# sensor_board_v0_8.net
KiCad netlist of a schematic drawn in EAGLE
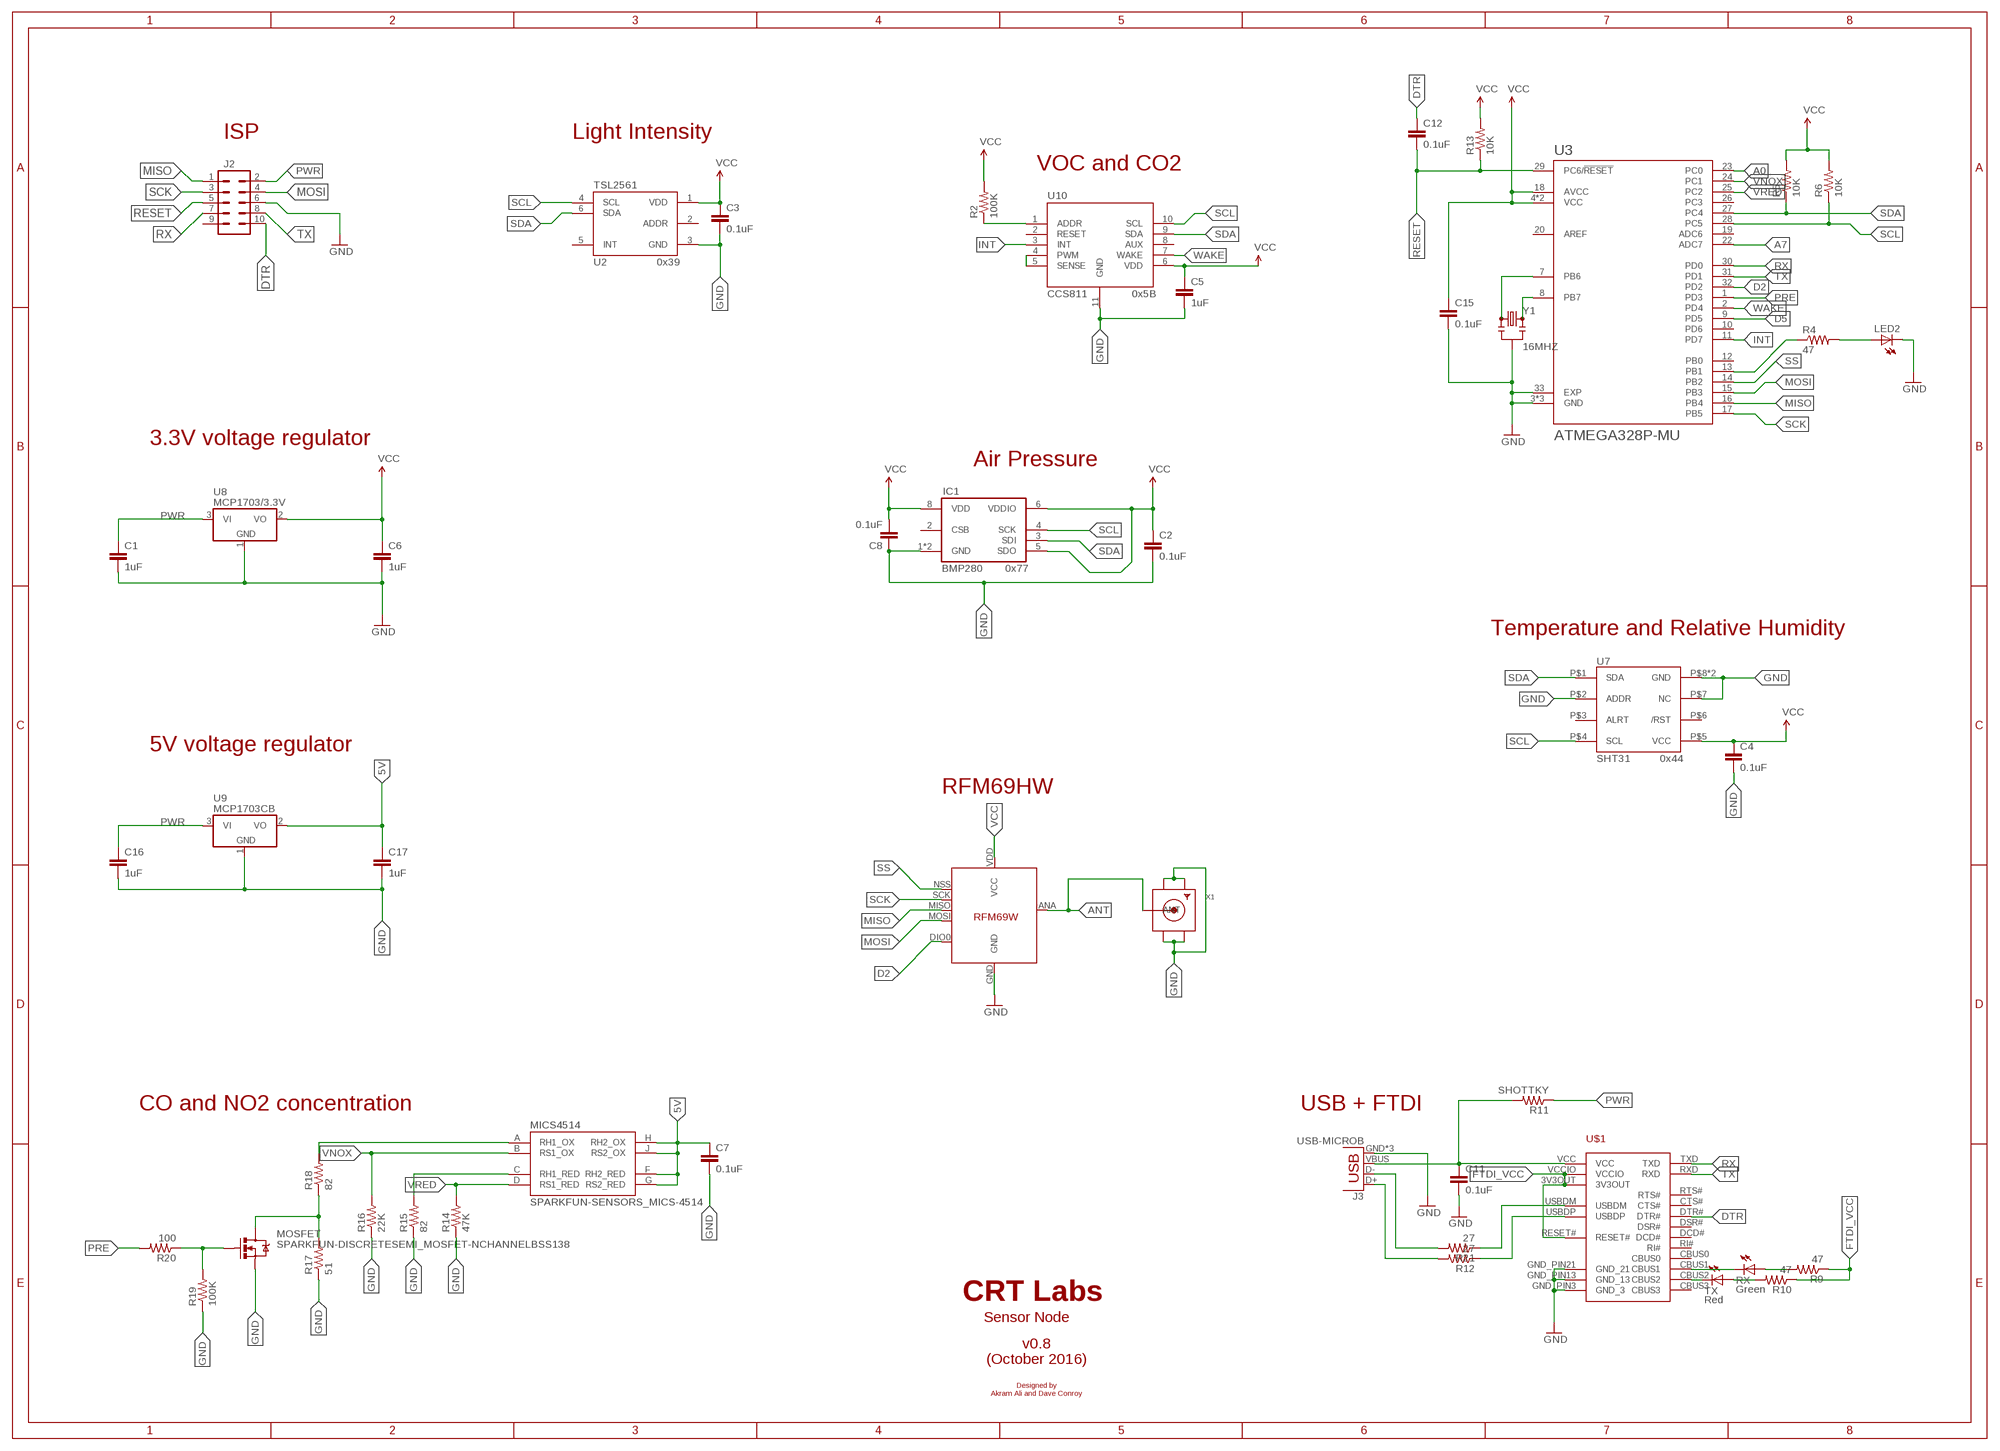
[diagram p0: schematic, sheet 1]

(export (version "E")
  (design (tool "Eeschema 10.0.6"))
  (components
    (comp (ref "C1")
      (value "1uF")
      (footprint "eagle-import:0805")
      (libsource (lib "eagle-import") (part "CAP0805"))
    )
    (comp (ref "C2")
      (value "0.1uF")
      (footprint "eagle-import:0805")
      (libsource (lib "eagle-import") (part "SparkFun-Passives_CAP0805"))
    )
    (comp (ref "C3")
      (value "0.1uF")
      (footprint "eagle-import:0805")
      (libsource (lib "eagle-import") (part "SparkFun-Passives_CAP0805"))
    )
    (comp (ref "C4")
      (value "0.1uF")
      (footprint "eagle-import:0805")
      (libsource (lib "eagle-import") (part "SparkFun-Passives_CAP0805"))
    )
    (comp (ref "C5")
      (value "1uF")
      (footprint "eagle-import:0805")
      (libsource (lib "eagle-import") (part "SparkFun-Passives_CAP0805"))
    )
    (comp (ref "C6")
      (value "1uF")
      (footprint "eagle-import:0805")
      (libsource (lib "eagle-import") (part "CAP0805"))
    )
    (comp (ref "C7")
      (value "0.1uF")
      (footprint "eagle-import:0805")
      (libsource (lib "eagle-import") (part "SparkFun-Passives_CAP0805"))
    )
    (comp (ref "C8")
      (value "0.1uF")
      (footprint "eagle-import:0805")
      (libsource (lib "eagle-import") (part "SparkFun-Passives_CAP0805"))
    )
    (comp (ref "C11")
      (value "0.1uF")
      (footprint "eagle-import:0805")
      (libsource (lib "eagle-import") (part "CAP0805"))
    )
    (comp (ref "C12")
      (value "0.1uF")
      (footprint "eagle-import:0805")
      (libsource (lib "eagle-import") (part "SparkFun-Passives_CAP0805"))
    )
    (comp (ref "C15")
      (value "0.1uF")
      (footprint "eagle-import:0805")
      (libsource (lib "eagle-import") (part "SparkFun-Passives_CAP0805"))
    )
    (comp (ref "C16")
      (value "1uF")
      (footprint "eagle-import:0805")
      (libsource (lib "eagle-import") (part "CAP0805"))
    )
    (comp (ref "C17")
      (value "1uF")
      (footprint "eagle-import:0805")
      (libsource (lib "eagle-import") (part "CAP0805"))
    )
    (comp (ref "IC1")
      (value "BMP280")
      (footprint "eagle-import:BMP280")
      (libsource (lib "eagle-import") (part "BMP280"))
    )
    (comp (ref "J2")
      (value "M05X2PTH")
      (footprint "eagle-import:AVR_ICSP")
      (libsource (lib "eagle-import") (part "M05X2PTH"))
    )
    (comp (ref "J3")
      (value "USB-MICROB")
      (footprint "eagle-import:USB-MICROB")
      (libsource (lib "eagle-import") (part "USB-MICROB"))
    )
    (comp (ref "LED2")
      (value "LEDCHIPLED_0805")
      (footprint "eagle-import:CHIPLED_0805")
      (libsource (lib "eagle-import") (part "LEDCHIPLED_0805"))
    )
    (comp (ref "MICS4514")
      (value "SPARKFUN-SENSORS_MICS-4514")
      (footprint "eagle-import:SPARKFUN-SENSORS_MICS_10-SMD")
      (libsource (lib "eagle-import") (part "SPARKFUN-SENSORS_MICS-4514"))
    )
    (comp (ref "MOSFET")
      (value "SPARKFUN-DISCRETESEMI_MOSFET-NCHANNELBSS138")
      (footprint "eagle-import:SPARKFUN-DISCRETESEMI_SOT23-3")
      (libsource (lib "eagle-import") (part "SPARKFUN-DISCRETESEMI_MOSFET-NCHANNELBSS138"))
    )
    (comp (ref "R2")
      (value "100K")
      (footprint "eagle-import:0805")
      (libsource (lib "eagle-import") (part "RESISTOR0805-RES"))
    )
    (comp (ref "R4")
      (value "47")
      (footprint "eagle-import:0805")
      (libsource (lib "eagle-import") (part "SparkFun-Resistors_RESISTOR0805-RES"))
    )
    (comp (ref "R5")
      (value "10K")
      (footprint "eagle-import:0805")
      (libsource (lib "eagle-import") (part "SparkFun-Resistors_RESISTOR0805-RES"))
    )
    (comp (ref "R6")
      (value "10K")
      (footprint "eagle-import:0805")
      (libsource (lib "eagle-import") (part "SparkFun-Resistors_RESISTOR0805-RES"))
    )
    (comp (ref "R9")
      (value "47")
      (footprint "eagle-import:0805")
      (libsource (lib "eagle-import") (part "RESISTOR0805-RES"))
    )
    (comp (ref "R10")
      (value "47")
      (footprint "eagle-import:0805")
      (libsource (lib "eagle-import") (part "RESISTOR0805-RES"))
    )
    (comp (ref "R11")
      (value "SHOTTKY")
      (footprint "eagle-import:0805")
      (libsource (lib "eagle-import") (part "RESISTOR0805-RES"))
    )
    (comp (ref "R12")
      (value "27")
      (footprint "eagle-import:0805")
      (libsource (lib "eagle-import") (part "RESISTOR0805-RES"))
    )
    (comp (ref "R13")
      (value "10K")
      (footprint "eagle-import:0805")
      (libsource (lib "eagle-import") (part "RESISTOR0805-RES"))
    )
    (comp (ref "R14")
      (value "47K")
      (footprint "eagle-import:0805")
      (libsource (lib "eagle-import") (part "RESISTOR0805-RES"))
    )
    (comp (ref "R15")
      (value "82")
      (footprint "eagle-import:0805")
      (libsource (lib "eagle-import") (part "RESISTOR0805-RES"))
    )
    (comp (ref "R16")
      (value "22K")
      (footprint "eagle-import:0805")
      (libsource (lib "eagle-import") (part "RESISTOR0805-RES"))
    )
    (comp (ref "R17")
      (value "51")
      (footprint "eagle-import:0805")
      (libsource (lib "eagle-import") (part "RESISTOR0805-RES"))
    )
    (comp (ref "R18")
      (value "82")
      (footprint "eagle-import:0805")
      (libsource (lib "eagle-import") (part "RESISTOR0805-RES"))
    )
    (comp (ref "R19")
      (value "100K")
      (footprint "eagle-import:0805")
      (libsource (lib "eagle-import") (part "RESISTOR0805-RES"))
    )
    (comp (ref "R20")
      (value "100")
      (footprint "eagle-import:0805")
      (libsource (lib "eagle-import") (part "RESISTOR0805-RES"))
    )
    (comp (ref "R21")
      (value "27")
      (footprint "eagle-import:0805")
      (libsource (lib "eagle-import") (part "RESISTOR0805-RES"))
    )
    (comp (ref "RX")
      (value "Green")
      (footprint "eagle-import:CHIPLED_0805")
      (libsource (lib "eagle-import") (part "LEDCHIPLED_0805"))
    )
    (comp (ref "TX")
      (value "Red")
      (footprint "eagle-import:CHIPLED_0805")
      (libsource (lib "eagle-import") (part "LEDCHIPLED_0805"))
    )
    (comp (ref "U$1")
      (value "FT231XQ-R")
      (footprint "eagle-import:FTDI_FT231XQ-R_PACKAGE")
      (libsource (lib "eagle-import") (part "FT231XQ-R"))
    )
    (comp (ref "U2")
      (value "TSL2561")
      (footprint "eagle-import:FN-6")
      (fields (field (name "MANF") "AMS-TAOS-USA-Inc.") (field (name "MPN") "TSL2561FN"))
      (libsource (lib "eagle-import") (part "TSL2561FN"))
    )
    (comp (ref "U3")
      (value "ATMEGA328P-MU")
      (footprint "eagle-import:QFN50P500X500X100-33N")
      (fields (field (name "MF") "Atmel"))
      (libsource (lib "eagle-import") (part "ATMEGA328P-MU"))
    )
    (comp (ref "U7")
      (value "SHT31")
      (footprint "eagle-import:SHT3X")
      (fields (field (name "MPN") "SHT31-DIS-B"))
      (libsource (lib "eagle-import") (part "SHT31-DIS"))
    )
    (comp (ref "U8")
      (value "MCP1703/3.3V")
      (footprint "eagle-import:SOT23")
      (fields (field (name "MPN") "MCP1703T-2502E/CB"))
      (libsource (lib "eagle-import") (part "MCP1703CB"))
    )
    (comp (ref "U9")
      (value "MCP1703CB")
      (footprint "eagle-import:SOT23")
      (fields (field (name "MPN") "MCP1703T-2502E/CB"))
      (libsource (lib "eagle-import") (part "MCP1703CB"))
    )
    (comp (ref "U10")
      (value "CCS811")
      (footprint "eagle-import:LGA")
      (libsource (lib "eagle-import") (part "CCS811-I2C"))
    )
    (comp (ref "U11")
      (value "RFM69HW")
      (footprint "eagle-import:LOWPOWERLAB_RFM69W-MINPADS")
      (libsource (lib "eagle-import") (part "LOWPOWERLAB_RFM69"))
    )
    (comp (ref "X1")
      (value "SMACONNECTOR_EDGE")
      (footprint "eagle-import:SMA_EDGELAUNCH")
      (libsource (lib "eagle-import") (part "SMACONNECTOR_EDGE"))
    )
    (comp (ref "Y1")
      (value "16MHZ")
      (footprint "eagle-import:RESONATOR-SMD")
      (libsource (lib "eagle-import") (part "RESONATOR16MHZ"))
    )
  )
  (nets
    (net (code "1") (name "5V") (class "Default")
      (node (ref "C17") (pin "1") (pinfunction "1_1") (pintype "passive"))
      (node (ref "C7") (pin "1") (pinfunction "1_1") (pintype "passive"))
      (node (ref "MICS4514") (pin "F") (pinfunction "RH2_RED_F") (pintype "bidirectional"))
      (node (ref "MICS4514") (pin "G") (pinfunction "RS2_RED_G") (pintype "bidirectional"))
      (node (ref "MICS4514") (pin "H") (pinfunction "RH2_OX_H") (pintype "bidirectional"))
      (node (ref "MICS4514") (pin "J") (pinfunction "RS2_OX_J") (pintype "bidirectional"))
      (node (ref "U9") (pin "2") (pinfunction "VO_2") (pintype "passive"))
    )
    (net (code "2") (name "A0") (class "Default")
      (node (ref "U3") (pin "23") (pinfunction "PC0_23") (pintype "bidirectional"))
    )
    (net (code "3") (name "A7") (class "Default")
      (node (ref "U3") (pin "22") (pinfunction "ADC7_22") (pintype "bidirectional"))
    )
    (net (code "4") (name "ANT") (class "Default")
      (node (ref "U11") (pin "ANA") (pinfunction "ANT_ANA") (pintype "passive"))
      (node (ref "X1") (pin "P") (pinfunction "ANT_P") (pintype "bidirectional"))
    )
    (net (code "5") (name "D2") (class "Default")
      (node (ref "U11") (pin "DIO0") (pinfunction "DIO0_DIO0") (pintype "open_collector"))
      (node (ref "U3") (pin "32") (pinfunction "PD2_32") (pintype "bidirectional"))
    )
    (net (code "6") (name "D5") (class "Default")
      (node (ref "U3") (pin "9") (pinfunction "PD5_9") (pintype "bidirectional"))
    )
    (net (code "7") (name "DTR") (class "Default")
      (node (ref "C12") (pin "1") (pinfunction "1_1") (pintype "passive"))
      (node (ref "J2") (pin "10") (pinfunction "10_10") (pintype "passive"))
      (node (ref "U$1") (pin "DTR#") (pinfunction "DTR#_DTR#") (pintype "bidirectional"))
    )
    (net (code "8") (name "FTDI_VCC") (class "Default")
      (node (ref "R10") (pin "1") (pinfunction "1_1") (pintype "passive"))
      (node (ref "R9") (pin "1") (pinfunction "1_1") (pintype "passive"))
      (node (ref "U$1") (pin "3V3OUT") (pinfunction "3V3OUT_3V3OUT") (pintype "bidirectional"))
      (node (ref "U$1") (pin "RESET#") (pinfunction "RESET#_RESET#") (pintype "bidirectional"))
      (node (ref "U$1") (pin "VCCIO") (pinfunction "VCCIO_VCCIO") (pintype "bidirectional"))
    )
    (net (code "9") (name "GND") (class "Default")
      (node (ref "C1") (pin "2") (pinfunction "2_2") (pintype "passive"))
      (node (ref "C11") (pin "2") (pinfunction "2_2") (pintype "passive"))
      (node (ref "C15") (pin "2") (pinfunction "2_2") (pintype "passive"))
      (node (ref "C16") (pin "2") (pinfunction "2_2") (pintype "passive"))
      (node (ref "C17") (pin "2") (pinfunction "2_2") (pintype "passive"))
      (node (ref "C2") (pin "2") (pinfunction "2_2") (pintype "passive"))
      (node (ref "C3") (pin "2") (pinfunction "2_2") (pintype "passive"))
      (node (ref "C4") (pin "2") (pinfunction "2_2") (pintype "passive"))
      (node (ref "C5") (pin "2") (pinfunction "2_2") (pintype "passive"))
      (node (ref "C6") (pin "2") (pinfunction "2_2") (pintype "passive"))
      (node (ref "C7") (pin "2") (pinfunction "2_2") (pintype "passive"))
      (node (ref "C8") (pin "1") (pinfunction "1_1") (pintype "passive"))
      (node (ref "IC1") (pin "1") (pinfunction "GND_1") (pintype "power_in"))
      (node (ref "IC1") (pin "7") (pinfunction "GND_7") (pintype "power_in"))
      (node (ref "J2") (pin "6") (pinfunction "6_6") (pintype "passive"))
      (node (ref "J3") (pin "GND") (pinfunction "GND_GND") (pintype "bidirectional"))
      (node (ref "J3") (pin "MT1") (pinfunction "GND_MT1") (pintype "bidirectional"))
      (node (ref "J3") (pin "MT2") (pinfunction "GND_MT2") (pintype "bidirectional"))
      (node (ref "LED2") (pin "C") (pinfunction "C_C") (pintype "passive"))
      (node (ref "MOSFET") (pin "2") (pinfunction "S_2") (pintype "passive"))
      (node (ref "R14") (pin "1") (pinfunction "1_1") (pintype "passive"))
      (node (ref "R15") (pin "1") (pinfunction "1_1") (pintype "passive"))
      (node (ref "R16") (pin "1") (pinfunction "1_1") (pintype "passive"))
      (node (ref "R17") (pin "1") (pinfunction "1_1") (pintype "passive"))
      (node (ref "R19") (pin "1") (pinfunction "1_1") (pintype "passive"))
      (node (ref "U$1") (pin "GND_PIN13") (pinfunction "GND_13_GND_PIN13") (pintype "bidirectional"))
      (node (ref "U$1") (pin "GND_PIN21") (pinfunction "GND_21_GND_PIN21") (pintype "bidirectional"))
      (node (ref "U$1") (pin "GND_PIN3") (pinfunction "GND_3_GND_PIN3") (pintype "bidirectional"))
      (node (ref "U10") (pin "11") (pinfunction "GND_11") (pintype "bidirectional"))
      (node (ref "U11") (pin "GND") (pinfunction "GND_GND") (pintype "power_in"))
      (node (ref "U2") (pin "3") (pinfunction "GND_3") (pintype "power_in"))
      (node (ref "U3") (pin "21") (pinfunction "GND_21") (pintype "power_in"))
      (node (ref "U3") (pin "3") (pinfunction "GND_3") (pintype "power_in"))
      (node (ref "U3") (pin "33") (pinfunction "EXP_33") (pintype "power_in"))
      (node (ref "U3") (pin "5") (pinfunction "GND_5") (pintype "power_in"))
      (node (ref "U7") (pin "P$2") (pinfunction "ADDR_P$2") (pintype "bidirectional"))
      (node (ref "U7") (pin "P$7") (pinfunction "NC_P$7") (pintype "bidirectional"))
      (node (ref "U7") (pin "P$8") (pinfunction "GND_P$8") (pintype "bidirectional"))
      (node (ref "U7") (pin "PAD") (pinfunction "GND_PAD") (pintype "bidirectional"))
      (node (ref "U8") (pin "1") (pinfunction "GND_1") (pintype "passive"))
      (node (ref "U9") (pin "1") (pinfunction "GND_1") (pintype "passive"))
      (node (ref "X1") (pin "GND@1") (pinfunction "GND4_GND@1") (pintype "power_in"))
      (node (ref "X1") (pin "GND@2") (pinfunction "GND3_GND@2") (pintype "power_in"))
      (node (ref "X1") (pin "GND@3") (pinfunction "GND2_GND@3") (pintype "power_in"))
      (node (ref "X1") (pin "GND@4") (pinfunction "GND1_GND@4") (pintype "power_in"))
      (node (ref "Y1") (pin "2") (pinfunction "2_2") (pintype "passive"))
    )
    (net (code "10") (name "INT") (class "Default")
      (node (ref "U10") (pin "3") (pinfunction "INT_3") (pintype "bidirectional"))
      (node (ref "U3") (pin "11") (pinfunction "PD7_11") (pintype "bidirectional"))
    )
    (net (code "11") (name "MISO") (class "Default")
      (node (ref "J2") (pin "1") (pinfunction "1_1") (pintype "passive"))
      (node (ref "U11") (pin "MISO") (pinfunction "MISO_MISO") (pintype "input"))
      (node (ref "U3") (pin "16") (pinfunction "PB4_16") (pintype "bidirectional"))
    )
    (net (code "12") (name "MOSI") (class "Default")
      (node (ref "J2") (pin "4") (pinfunction "4_4") (pintype "passive"))
      (node (ref "U11") (pin "MOSI") (pinfunction "MOSI_MOSI") (pintype "output"))
      (node (ref "U3") (pin "15") (pinfunction "PB3_15") (pintype "bidirectional"))
    )
    (net (code "13") (name "Net-(C11-Pad1)") (class "Default")
      (node (ref "C11") (pin "1") (pinfunction "1_1") (pintype "passive"))
      (node (ref "J3") (pin "VBUS") (pinfunction "VBUS_VBUS") (pintype "bidirectional"))
      (node (ref "R11") (pin "2") (pinfunction "2_2") (pintype "passive"))
      (node (ref "U$1") (pin "VCC") (pinfunction "VCC_VCC") (pintype "bidirectional"))
    )
    (net (code "14") (name "Net-(J3-PadD+)") (class "Default")
      (node (ref "J3") (pin "D+") (pinfunction "D+_D+") (pintype "bidirectional"))
      (node (ref "R12") (pin "2") (pinfunction "2_2") (pintype "passive"))
    )
    (net (code "15") (name "Net-(J3-PadD-)") (class "Default")
      (node (ref "J3") (pin "D-") (pinfunction "D-_D-") (pintype "bidirectional"))
      (node (ref "R21") (pin "2") (pinfunction "2_2") (pintype "passive"))
    )
    (net (code "16") (name "Net-(LED2-PadA)") (class "Default")
      (node (ref "LED2") (pin "A") (pinfunction "A_A") (pintype "passive"))
      (node (ref "R4") (pin "2") (pinfunction "2_2") (pintype "passive"))
    )
    (net (code "17") (name "Net-(MICS4514-RH1_OX)") (class "Default")
      (node (ref "MICS4514") (pin "A") (pinfunction "RH1_OX_A") (pintype "bidirectional"))
      (node (ref "R18") (pin "2") (pinfunction "2_2") (pintype "passive"))
    )
    (net (code "18") (name "Net-(MICS4514-RH1_RED)") (class "Default")
      (node (ref "MICS4514") (pin "C") (pinfunction "RH1_RED_C") (pintype "bidirectional"))
      (node (ref "R15") (pin "2") (pinfunction "2_2") (pintype "passive"))
    )
    (net (code "19") (name "Net-(MOSFET-D)") (class "Default")
      (node (ref "MOSFET") (pin "3") (pinfunction "D_3") (pintype "passive"))
      (node (ref "R17") (pin "2") (pinfunction "2_2") (pintype "passive"))
      (node (ref "R18") (pin "1") (pinfunction "1_1") (pintype "passive"))
    )
    (net (code "20") (name "Net-(MOSFET-G)") (class "Default")
      (node (ref "MOSFET") (pin "1") (pinfunction "G_1") (pintype "passive"))
      (node (ref "R19") (pin "2") (pinfunction "2_2") (pintype "passive"))
      (node (ref "R20") (pin "1") (pinfunction "1_1") (pintype "passive"))
    )
    (net (code "21") (name "Net-(R9-Pad2)") (class "Default")
      (node (ref "R9") (pin "2") (pinfunction "2_2") (pintype "passive"))
      (node (ref "RX") (pin "A") (pinfunction "A_A") (pintype "passive"))
    )
    (net (code "22") (name "Net-(R10-Pad2)") (class "Default")
      (node (ref "R10") (pin "2") (pinfunction "2_2") (pintype "passive"))
      (node (ref "TX") (pin "A") (pinfunction "A_A") (pintype "passive"))
    )
    (net (code "23") (name "Net-(R12-Pad1)") (class "Default")
      (node (ref "R12") (pin "1") (pinfunction "1_1") (pintype "passive"))
      (node (ref "U$1") (pin "USBDP") (pinfunction "USBDP_USBDP") (pintype "bidirectional"))
    )
    (net (code "24") (name "Net-(R21-Pad1)") (class "Default")
      (node (ref "R21") (pin "1") (pinfunction "1_1") (pintype "passive"))
      (node (ref "U$1") (pin "USBDM") (pinfunction "USBDM_USBDM") (pintype "bidirectional"))
    )
    (net (code "25") (name "Net-(RX-PadC)") (class "Default")
      (node (ref "RX") (pin "C") (pinfunction "C_C") (pintype "passive"))
      (node (ref "U$1") (pin "CBUS1") (pinfunction "CBUS1_CBUS1") (pintype "bidirectional"))
    )
    (net (code "26") (name "Net-(TX-PadC)") (class "Default")
      (node (ref "TX") (pin "C") (pinfunction "C_C") (pintype "passive"))
      (node (ref "U$1") (pin "CBUS2") (pinfunction "CBUS2_CBUS2") (pintype "bidirectional"))
    )
    (net (code "27") (name "Net-(U3-PB1)") (class "Default")
      (node (ref "R4") (pin "1") (pinfunction "1_1") (pintype "passive"))
      (node (ref "U3") (pin "13") (pinfunction "PB1_13") (pintype "bidirectional"))
    )
    (net (code "28") (name "Net-(U3-PB6)") (class "Default")
      (node (ref "U3") (pin "7") (pinfunction "PB6_7") (pintype "bidirectional"))
      (node (ref "Y1") (pin "1") (pinfunction "1_1") (pintype "passive"))
    )
    (net (code "29") (name "Net-(U3-PB7)") (class "Default")
      (node (ref "U3") (pin "8") (pinfunction "PB7_8") (pintype "bidirectional"))
      (node (ref "Y1") (pin "3") (pinfunction "3_3") (pintype "passive"))
    )
    (net (code "30") (name "Net-(U10-ADDR)") (class "Default")
      (node (ref "R2") (pin "1") (pinfunction "1_1") (pintype "passive"))
      (node (ref "U10") (pin "1") (pinfunction "ADDR_1") (pintype "bidirectional"))
    )
    (net (code "31") (name "Net-(U10-PWM)") (class "Default")
      (node (ref "U10") (pin "4") (pinfunction "PWM_4") (pintype "bidirectional"))
      (node (ref "U10") (pin "5") (pinfunction "SENSE_5") (pintype "bidirectional"))
    )
    (net (code "32") (name "PRE") (class "Default")
      (node (ref "R20") (pin "2") (pinfunction "2_2") (pintype "passive"))
      (node (ref "U3") (pin "1") (pinfunction "PD3_1") (pintype "bidirectional"))
    )
    (net (code "33") (name "PWR") (class "Default")
      (node (ref "C1") (pin "1") (pinfunction "1_1") (pintype "passive"))
      (node (ref "C16") (pin "1") (pinfunction "1_1") (pintype "passive"))
      (node (ref "J2") (pin "2") (pinfunction "2_2") (pintype "passive"))
      (node (ref "R11") (pin "1") (pinfunction "1_1") (pintype "passive"))
      (node (ref "U8") (pin "3") (pinfunction "VI_3") (pintype "input"))
      (node (ref "U9") (pin "3") (pinfunction "VI_3") (pintype "input"))
    )
    (net (code "34") (name "RESET") (class "Default")
      (node (ref "C12") (pin "2") (pinfunction "2_2") (pintype "passive"))
      (node (ref "J2") (pin "5") (pinfunction "5_5") (pintype "passive"))
      (node (ref "R13") (pin "1") (pinfunction "1_1") (pintype "passive"))
      (node (ref "U3") (pin "29") (pinfunction "PC6/~{RESET}_29") (pintype "bidirectional"))
    )
    (net (code "35") (name "RX") (class "Default")
      (node (ref "J2") (pin "7") (pinfunction "7_7") (pintype "passive"))
      (node (ref "U$1") (pin "TXD") (pinfunction "TXD_TXD") (pintype "bidirectional"))
      (node (ref "U3") (pin "30") (pinfunction "PD0_30") (pintype "bidirectional"))
    )
    (net (code "36") (name "SCK") (class "Default")
      (node (ref "J2") (pin "3") (pinfunction "3_3") (pintype "passive"))
      (node (ref "U11") (pin "SCK") (pinfunction "SCK_SCK") (pintype "input"))
      (node (ref "U3") (pin "17") (pinfunction "PB5_17") (pintype "bidirectional"))
    )
    (net (code "37") (name "SCL") (class "Default")
      (node (ref "IC1") (pin "4") (pinfunction "SCK_4") (pintype "bidirectional"))
      (node (ref "R6") (pin "1") (pinfunction "1_1") (pintype "passive"))
      (node (ref "U10") (pin "10") (pinfunction "SCL_10") (pintype "bidirectional"))
      (node (ref "U2") (pin "4") (pinfunction "SCL_4") (pintype "input"))
      (node (ref "U3") (pin "28") (pinfunction "PC5_28") (pintype "bidirectional"))
      (node (ref "U7") (pin "P$4") (pinfunction "SCL_P$4") (pintype "bidirectional"))
    )
    (net (code "38") (name "SDA") (class "Default")
      (node (ref "IC1") (pin "3") (pinfunction "SDI_3") (pintype "bidirectional"))
      (node (ref "R5") (pin "1") (pinfunction "1_1") (pintype "passive"))
      (node (ref "U10") (pin "9") (pinfunction "SDA_9") (pintype "bidirectional"))
      (node (ref "U2") (pin "6") (pinfunction "SDA_6") (pintype "bidirectional"))
      (node (ref "U3") (pin "27") (pinfunction "PC4_27") (pintype "bidirectional"))
      (node (ref "U7") (pin "P$1") (pinfunction "SDA_P$1") (pintype "bidirectional"))
    )
    (net (code "39") (name "SS") (class "Default")
      (node (ref "U11") (pin "NSS") (pinfunction "SEL_NSS") (pintype "input"))
      (node (ref "U3") (pin "14") (pinfunction "PB2_14") (pintype "bidirectional"))
    )
    (net (code "40") (name "TX") (class "Default")
      (node (ref "J2") (pin "8") (pinfunction "8_8") (pintype "passive"))
      (node (ref "U$1") (pin "RXD") (pinfunction "RXD_RXD") (pintype "bidirectional"))
      (node (ref "U3") (pin "31") (pinfunction "PD1_31") (pintype "bidirectional"))
    )
    (net (code "41") (name "VCC") (class "Default")
      (node (ref "C15") (pin "1") (pinfunction "1_1") (pintype "passive"))
      (node (ref "C2") (pin "1") (pinfunction "1_1") (pintype "passive"))
      (node (ref "C3") (pin "1") (pinfunction "1_1") (pintype "passive"))
      (node (ref "C4") (pin "1") (pinfunction "1_1") (pintype "passive"))
      (node (ref "C5") (pin "1") (pinfunction "1_1") (pintype "passive"))
      (node (ref "C6") (pin "1") (pinfunction "1_1") (pintype "passive"))
      (node (ref "C8") (pin "2") (pinfunction "2_2") (pintype "passive"))
      (node (ref "IC1") (pin "5") (pinfunction "SDO_5") (pintype "input"))
      (node (ref "IC1") (pin "6") (pinfunction "VDDIO_6") (pintype "power_in"))
      (node (ref "IC1") (pin "8") (pinfunction "VDD_8") (pintype "power_in"))
      (node (ref "R13") (pin "2") (pinfunction "2_2") (pintype "passive"))
      (node (ref "R2") (pin "2") (pinfunction "2_2") (pintype "passive"))
      (node (ref "R5") (pin "2") (pinfunction "2_2") (pintype "passive"))
      (node (ref "R6") (pin "2") (pinfunction "2_2") (pintype "passive"))
      (node (ref "U10") (pin "6") (pinfunction "VDD_6") (pintype "bidirectional"))
      (node (ref "U11") (pin "VDD") (pinfunction "VCC_VDD") (pintype "power_in"))
      (node (ref "U2") (pin "1") (pinfunction "VDD_1") (pintype "power_in"))
      (node (ref "U3") (pin "18") (pinfunction "AVCC_18") (pintype "power_in"))
      (node (ref "U3") (pin "4") (pinfunction "VCC_4") (pintype "power_in"))
      (node (ref "U3") (pin "6") (pinfunction "VCC_6") (pintype "power_in"))
      (node (ref "U7") (pin "P$5") (pinfunction "VCC_P$5") (pintype "bidirectional"))
      (node (ref "U8") (pin "2") (pinfunction "VO_2") (pintype "passive"))
    )
    (net (code "42") (name "VNOX") (class "Default")
      (node (ref "MICS4514") (pin "B") (pinfunction "RS1_OX_B") (pintype "bidirectional"))
      (node (ref "R16") (pin "2") (pinfunction "2_2") (pintype "passive"))
      (node (ref "U3") (pin "24") (pinfunction "PC1_24") (pintype "bidirectional"))
    )
    (net (code "43") (name "VRED") (class "Default")
      (node (ref "MICS4514") (pin "D") (pinfunction "RS1_RED_D") (pintype "bidirectional"))
      (node (ref "R14") (pin "2") (pinfunction "2_2") (pintype "passive"))
      (node (ref "U3") (pin "25") (pinfunction "PC2_25") (pintype "bidirectional"))
    )
    (net (code "44") (name "WAKE") (class "Default")
      (node (ref "U10") (pin "7") (pinfunction "WAKE_7") (pintype "bidirectional"))
      (node (ref "U3") (pin "2") (pinfunction "PD4_2") (pintype "bidirectional"))
    )
    (net (code "45") (name "unconnected-(IC1-CSB-Pad2)") (class "Default")
      (node (ref "IC1") (pin "2") (pinfunction "CSB_2") (pintype "input"))
    )
    (net (code "46") (name "unconnected-(J2-Pad9)") (class "Default")
      (node (ref "J2") (pin "9") (pinfunction "9_9") (pintype "passive"))
    )
    (net (code "47") (name "unconnected-(U$1-PadCBUS0)") (class "Default")
      (node (ref "U$1") (pin "CBUS0") (pinfunction "CBUS0_CBUS0") (pintype "bidirectional"))
    )
    (net (code "48") (name "unconnected-(U$1-PadCBUS3)") (class "Default")
      (node (ref "U$1") (pin "CBUS3") (pinfunction "CBUS3_CBUS3") (pintype "bidirectional"))
    )
    (net (code "49") (name "unconnected-(U$1-PadCTS#)") (class "Default")
      (node (ref "U$1") (pin "CTS#") (pinfunction "CTS#_CTS#") (pintype "bidirectional"))
    )
    (net (code "50") (name "unconnected-(U$1-PadDCD#)") (class "Default")
      (node (ref "U$1") (pin "DCD#") (pinfunction "DCD#_DCD#") (pintype "bidirectional"))
    )
    (net (code "51") (name "unconnected-(U$1-PadDSR#)") (class "Default")
      (node (ref "U$1") (pin "DSR#") (pinfunction "DSR#_DSR#") (pintype "bidirectional"))
    )
    (net (code "52") (name "unconnected-(U$1-PadRI#)") (class "Default")
      (node (ref "U$1") (pin "RI#") (pinfunction "RI#_RI#") (pintype "bidirectional"))
    )
    (net (code "53") (name "unconnected-(U$1-PadRTS#)") (class "Default")
      (node (ref "U$1") (pin "RTS#") (pinfunction "RTS#_RTS#") (pintype "bidirectional"))
    )
    (net (code "54") (name "unconnected-(U2-ADDR-Pad2)") (class "Default")
      (node (ref "U2") (pin "2") (pinfunction "ADDR_2") (pintype "input"))
    )
    (net (code "55") (name "unconnected-(U2-INT-Pad5)") (class "Default")
      (node (ref "U2") (pin "5") (pinfunction "INT_5") (pintype "output"))
    )
    (net (code "56") (name "unconnected-(U3-ADC6-Pad19)") (class "Default")
      (node (ref "U3") (pin "19") (pinfunction "ADC6_19") (pintype "bidirectional"))
    )
    (net (code "57") (name "unconnected-(U3-AREF-Pad20)") (class "Default")
      (node (ref "U3") (pin "20") (pinfunction "AREF_20") (pintype "input"))
    )
    (net (code "58") (name "unconnected-(U3-PB0-Pad12)") (class "Default")
      (node (ref "U3") (pin "12") (pinfunction "PB0_12") (pintype "bidirectional"))
    )
    (net (code "59") (name "unconnected-(U3-PC3-Pad26)") (class "Default")
      (node (ref "U3") (pin "26") (pinfunction "PC3_26") (pintype "bidirectional"))
    )
    (net (code "60") (name "unconnected-(U3-PD6-Pad10)") (class "Default")
      (node (ref "U3") (pin "10") (pinfunction "PD6_10") (pintype "bidirectional"))
    )
    (net (code "61") (name "unconnected-(U7-ALRT-PadP$3)") (class "Default")
      (node (ref "U7") (pin "P$3") (pinfunction "ALRT_P$3") (pintype "bidirectional"))
    )
    (net (code "62") (name "unconnected-(U7-{slash}RST-PadP$6)") (class "Default")
      (node (ref "U7") (pin "P$6") (pinfunction "/RST_P$6") (pintype "bidirectional"))
    )
    (net (code "63") (name "unconnected-(U10-AUX-Pad8)") (class "Default")
      (node (ref "U10") (pin "8") (pinfunction "AUX_8") (pintype "bidirectional"))
    )
    (net (code "64") (name "unconnected-(U10-RESET-Pad2)") (class "Default")
      (node (ref "U10") (pin "2") (pinfunction "RESET_2") (pintype "bidirectional"))
    )
  )
)
